# SCH_FMC-R2_MAIN_2026-02-22.net
KiCad netlist of a schematic drawn in EasyEDA
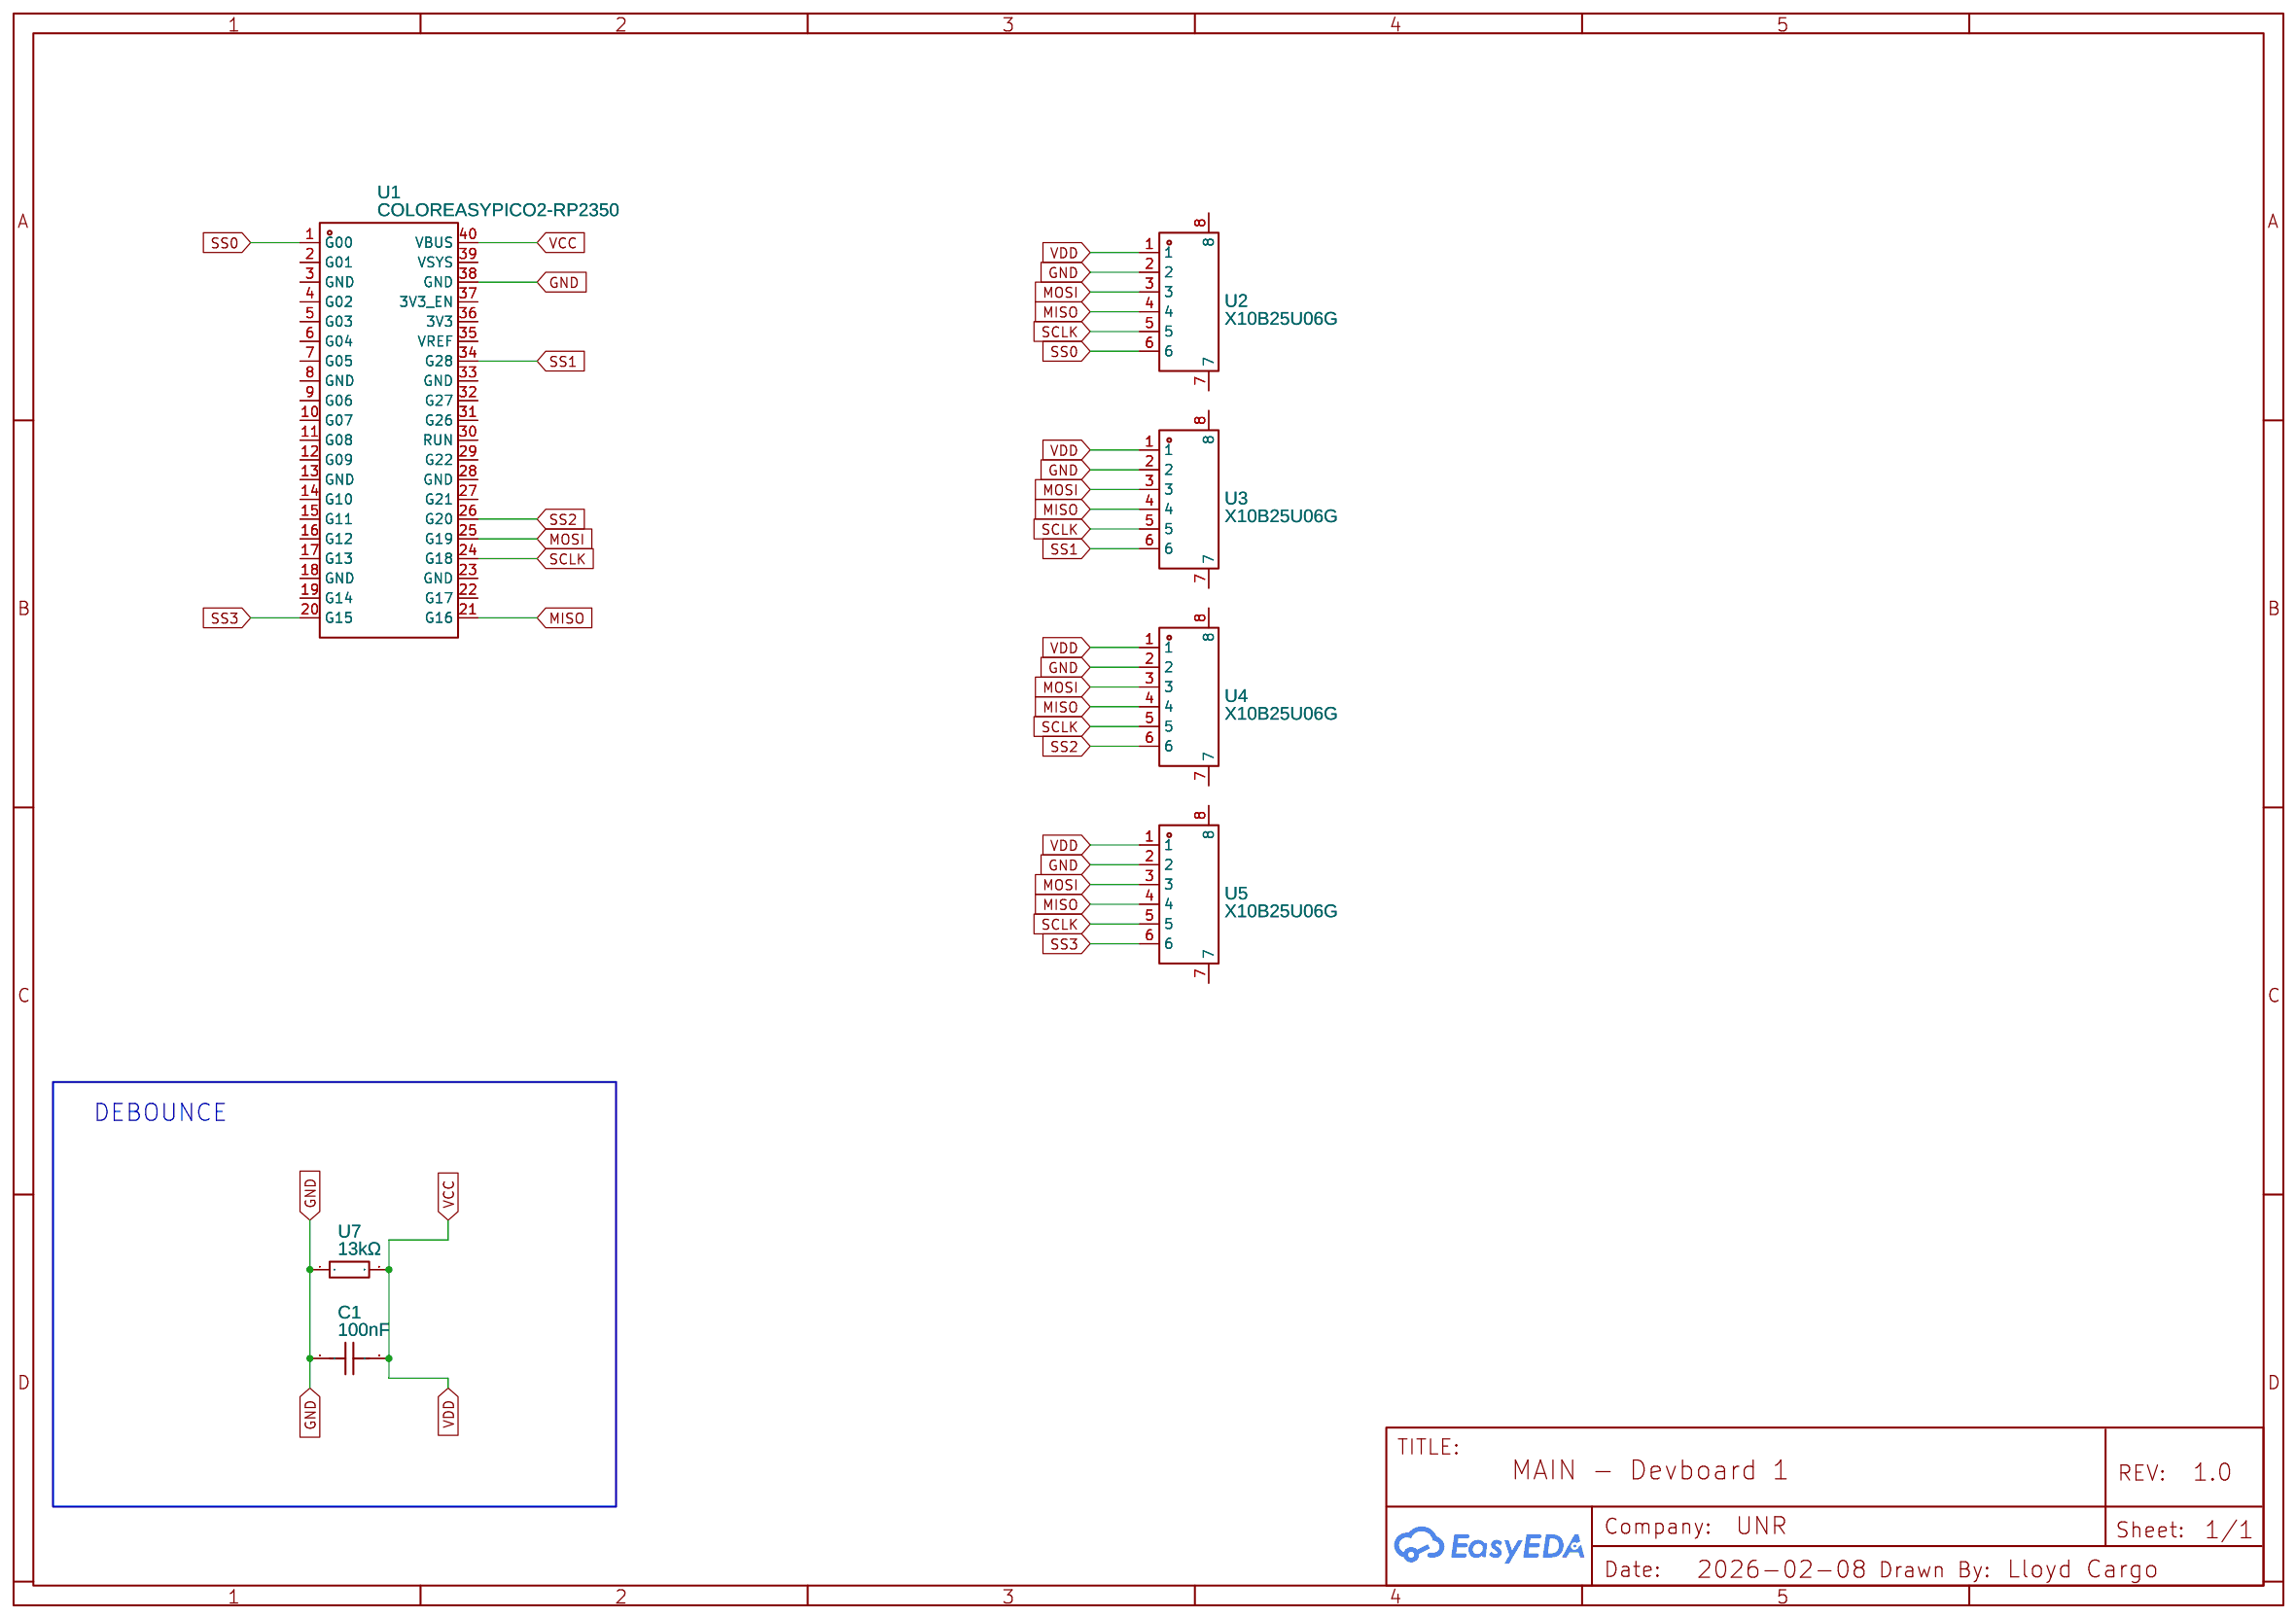
[diagram p0: MAIN]
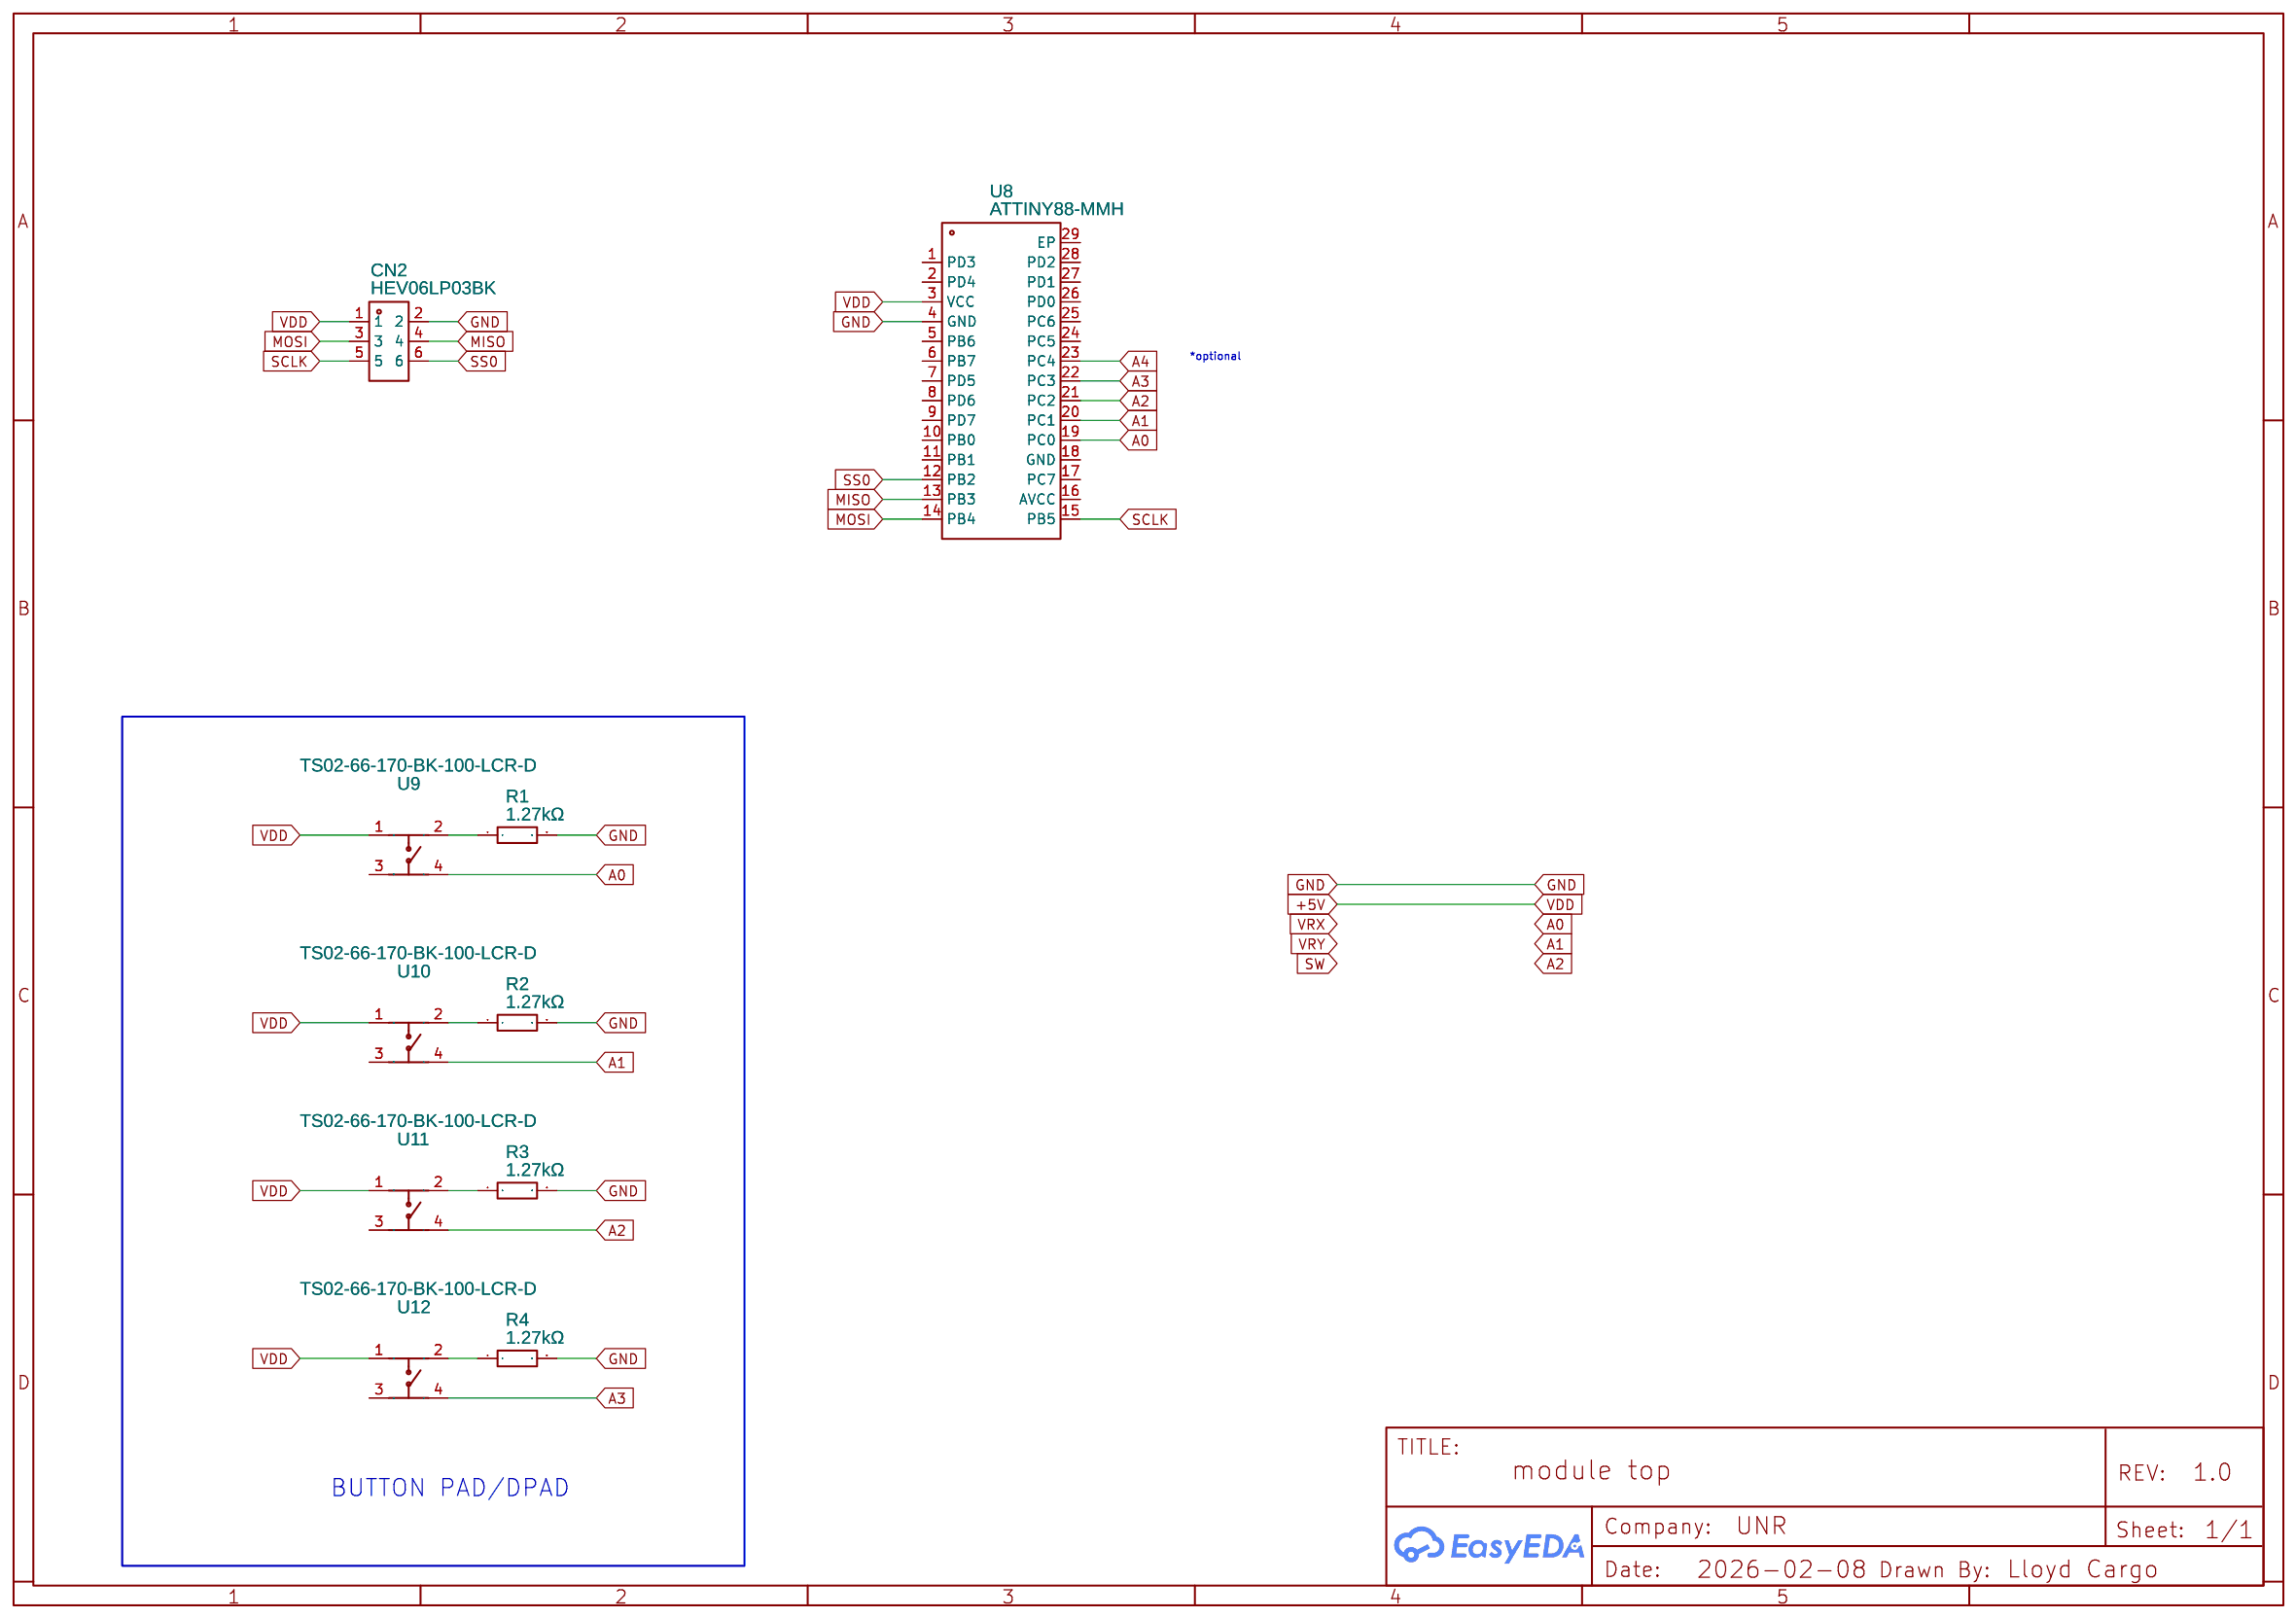
[diagram p1: module top]
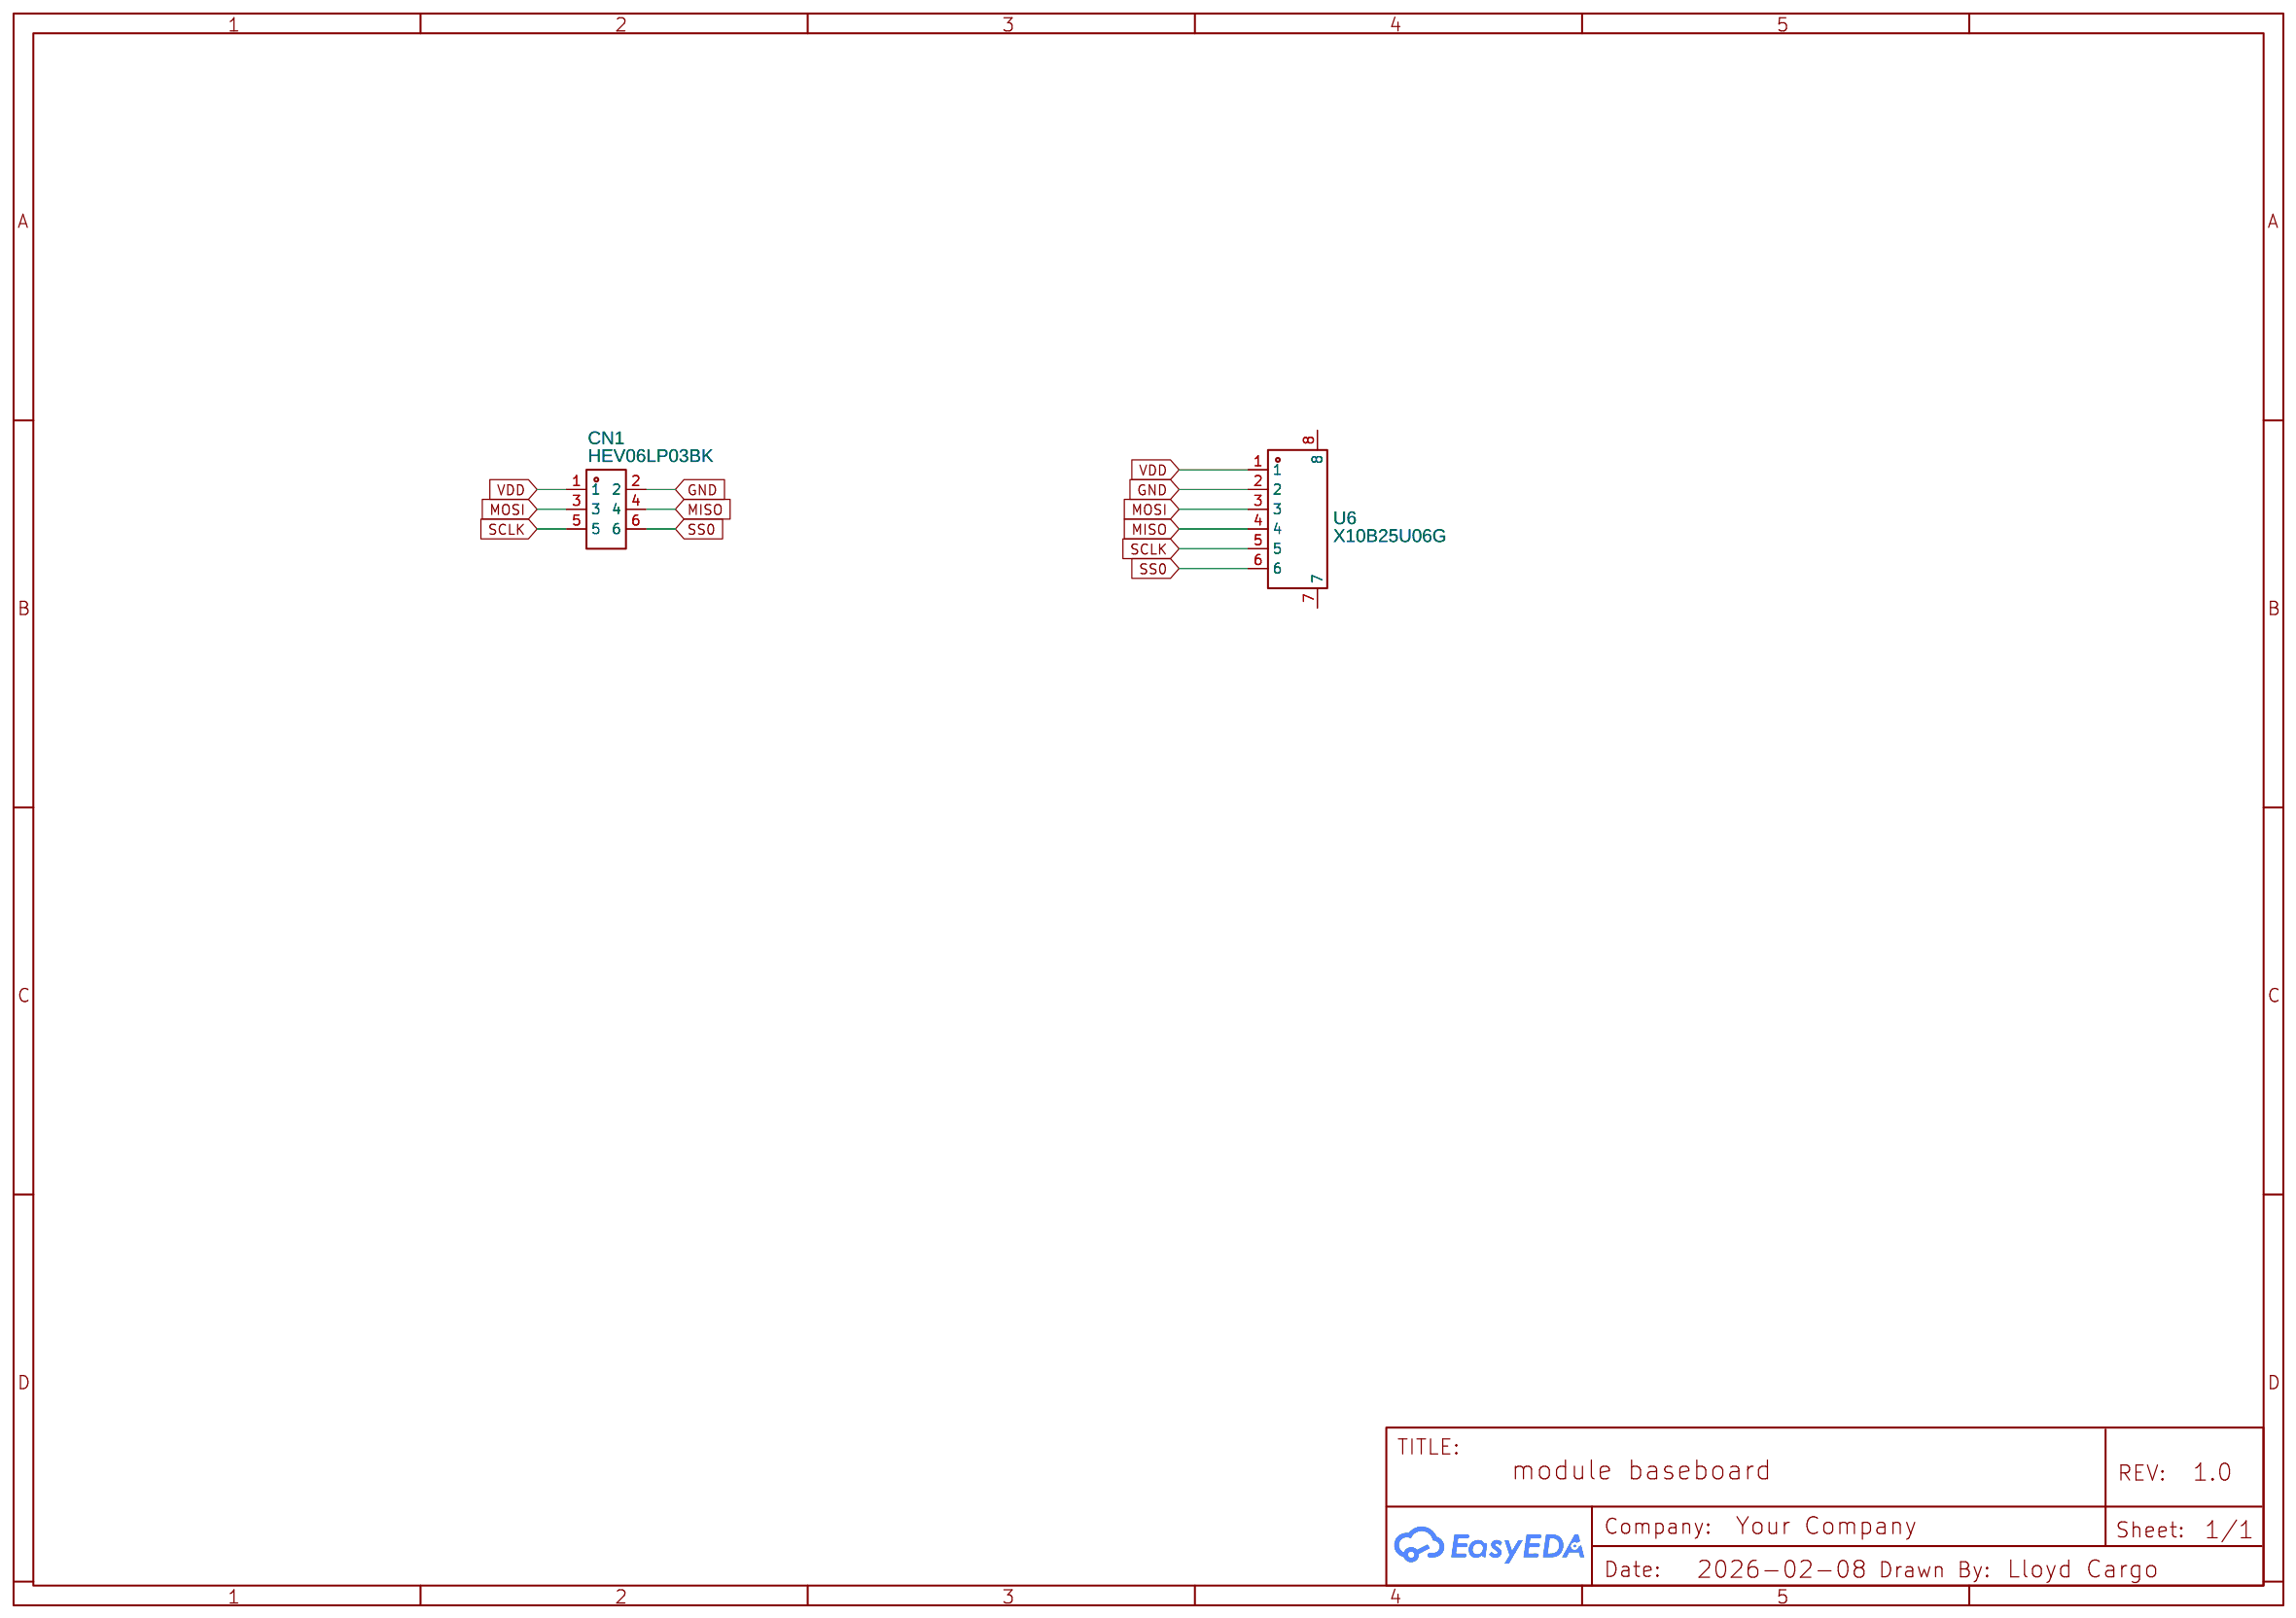
[diagram p2: module baseboard]

(export (version "E")
  (design (tool "Eeschema 10.0.6"))
  (components
    (comp (ref "C1")
      (value "100nF")
      (fields
        (field (name "Manufacturer Part") "GCG188R92A104KA03D")
        (field (name "Manufacturer") "muRata(村田)")
      )
      (libsource (lib "") (part "GCG188R92A104KA03D"))
    )
    (comp (ref "U1")
      (value "COLOREASYPICO2-RP2350")
      (fields
        (field (name "Manufacturer Part") "ColorEasyPico2-RP2350")
        (field (name "Manufacturer") "立创开发板")
      )
      (libsource (lib "") (part "COLOREASYPICO2-RP2350"))
    )
    (comp (ref "U2")
      (value "X10B25U06G")
      (fields (field (name "Manufacturer") "XKB Connection(中国星坤)"))
      (libsource (lib "") (part "X10B25U06G"))
    )
    (comp (ref "U3")
      (value "X10B25U06G")
      (fields (field (name "Manufacturer") "XKB Connection(中国星坤)"))
      (libsource (lib "") (part "X10B25U06G"))
    )
    (comp (ref "U4")
      (value "X10B25U06G")
      (fields (field (name "Manufacturer") "XKB Connection(中国星坤)"))
      (libsource (lib "") (part "X10B25U06G"))
    )
    (comp (ref "U5")
      (value "X10B25U06G")
      (fields (field (name "Manufacturer") "XKB Connection(中国星坤)"))
      (libsource (lib "") (part "X10B25U06G"))
    )
    (comp (ref "U7")
      (value "13kΩ")
      (fields (field (name "Manufacturer Part") "HPCR0805F13K0K9") (field (name "Manufacturer") "RESI(开步睿思)"))
      (libsource (lib "") (part "HPCR0805F13K0K9"))
    )
    (comp (ref "CN2")
      (value "HEV06LP03BK")
      (fields (field (name "Manufacturer") "WingTAT(格林柏)"))
      (libsource (lib "") (part "HEV06LP03BK"))
    )
    (comp (ref "R1")
      (value "1.27kΩ")
      (fields (field (name "Manufacturer Part") "RC0603FR-071K27L") (field (name "Manufacturer") "YAGEO(国巨)"))
      (libsource (lib "") (part "RC0603FR-071K27L"))
    )
    (comp (ref "R2")
      (value "1.27kΩ")
      (fields (field (name "Manufacturer Part") "RC0603FR-071K27L") (field (name "Manufacturer") "YAGEO(国巨)"))
      (libsource (lib "") (part "RC0603FR-071K27L"))
    )
    (comp (ref "R3")
      (value "1.27kΩ")
      (fields (field (name "Manufacturer Part") "RC0603FR-071K27L") (field (name "Manufacturer") "YAGEO(国巨)"))
      (libsource (lib "") (part "RC0603FR-071K27L"))
    )
    (comp (ref "R4")
      (value "1.27kΩ")
      (fields (field (name "Manufacturer Part") "RC0603FR-071K27L") (field (name "Manufacturer") "YAGEO(国巨)"))
      (libsource (lib "") (part "RC0603FR-071K27L"))
    )
    (comp (ref "U8")
      (value "ATTINY88-MMH")
      (fields (field (name "Manufacturer") "MICROCHIP(美国微芯)"))
      (libsource (lib "") (part "ATTINY88-MMH"))
    )
    (comp (ref "U9")
      (value "TS02-66-170-BK-100-LCR-D")
      (fields (field (name "Manufacturer") "CUI"))
      (libsource (lib "") (part "TS02-66-170-BK-100-LCR-D"))
    )
    (comp (ref "U10")
      (value "TS02-66-170-BK-100-LCR-D")
      (fields (field (name "Manufacturer") "CUI"))
      (libsource (lib "") (part "TS02-66-170-BK-100-LCR-D"))
    )
    (comp (ref "U11")
      (value "TS02-66-170-BK-100-LCR-D")
      (fields (field (name "Manufacturer") "CUI"))
      (libsource (lib "") (part "TS02-66-170-BK-100-LCR-D"))
    )
    (comp (ref "U12")
      (value "TS02-66-170-BK-100-LCR-D")
      (fields (field (name "Manufacturer") "CUI"))
      (libsource (lib "") (part "TS02-66-170-BK-100-LCR-D"))
    )
    (comp (ref "CN1")
      (value "HEV06LP03BK")
      (fields (field (name "Manufacturer") "WingTAT(格林柏)"))
      (libsource (lib "") (part "HEV06LP03BK"))
    )
    (comp (ref "U6")
      (value "X10B25U06G")
      (fields (field (name "Manufacturer") "XKB Connection(中国星坤)"))
      (libsource (lib "") (part "X10B25U06G"))
    )
  )
  (nets
    (net (code "1") (name "+5V") (class "Default")
      (node (ref "C1") (pin "2") (pinfunction "2_2") (pintype "unspecified"))
      (node (ref "CN1") (pin "1") (pinfunction "1_1") (pintype "unspecified"))
      (node (ref "CN2") (pin "1") (pinfunction "1_1") (pintype "unspecified"))
      (node (ref "U1") (pin "40") (pinfunction "VBUS_40") (pintype "unspecified"))
      (node (ref "U10") (pin "1") (pinfunction "1_1") (pintype "unspecified"))
      (node (ref "U11") (pin "1") (pinfunction "1_1") (pintype "unspecified"))
      (node (ref "U12") (pin "1") (pinfunction "1_1") (pintype "unspecified"))
      (node (ref "U2") (pin "1") (pinfunction "1_1") (pintype "unspecified"))
      (node (ref "U3") (pin "1") (pinfunction "1_1") (pintype "unspecified"))
      (node (ref "U4") (pin "1") (pinfunction "1_1") (pintype "unspecified"))
      (node (ref "U5") (pin "1") (pinfunction "1_1") (pintype "unspecified"))
      (node (ref "U6") (pin "1") (pinfunction "1_1") (pintype "unspecified"))
      (node (ref "U7") (pin "2") (pinfunction "2_2") (pintype "unspecified"))
      (node (ref "U8") (pin "3") (pinfunction "VCC_3") (pintype "unspecified"))
      (node (ref "U9") (pin "1") (pinfunction "1_1") (pintype "unspecified"))
    )
    (net (code "2") (name "A0") (class "Default")
      (node (ref "U8") (pin "19") (pinfunction "PC0_19") (pintype "unspecified"))
      (node (ref "U9") (pin "4") (pinfunction "4_4") (pintype "unspecified"))
    )
    (net (code "3") (name "A1") (class "Default")
      (node (ref "U10") (pin "4") (pinfunction "4_4") (pintype "unspecified"))
      (node (ref "U8") (pin "20") (pinfunction "PC1_20") (pintype "unspecified"))
    )
    (net (code "4") (name "A2") (class "Default")
      (node (ref "U11") (pin "4") (pinfunction "4_4") (pintype "unspecified"))
      (node (ref "U8") (pin "21") (pinfunction "PC2_21") (pintype "unspecified"))
    )
    (net (code "5") (name "A3") (class "Default")
      (node (ref "U12") (pin "4") (pinfunction "4_4") (pintype "unspecified"))
      (node (ref "U8") (pin "22") (pinfunction "PC3_22") (pintype "unspecified"))
    )
    (net (code "6") (name "A4") (class "Default")
      (node (ref "U8") (pin "23") (pinfunction "PC4_23") (pintype "unspecified"))
    )
    (net (code "7") (name "GND") (class "Default")
      (node (ref "C1") (pin "1") (pinfunction "1_1") (pintype "unspecified"))
      (node (ref "CN1") (pin "2") (pinfunction "2_2") (pintype "unspecified"))
      (node (ref "CN2") (pin "2") (pinfunction "2_2") (pintype "unspecified"))
      (node (ref "R1") (pin "2") (pinfunction "2_2") (pintype "unspecified"))
      (node (ref "R2") (pin "2") (pinfunction "2_2") (pintype "unspecified"))
      (node (ref "R3") (pin "2") (pinfunction "2_2") (pintype "unspecified"))
      (node (ref "R4") (pin "2") (pinfunction "2_2") (pintype "unspecified"))
      (node (ref "U1") (pin "38") (pinfunction "GND_38") (pintype "unspecified"))
      (node (ref "U2") (pin "2") (pinfunction "2_2") (pintype "unspecified"))
      (node (ref "U3") (pin "2") (pinfunction "2_2") (pintype "unspecified"))
      (node (ref "U4") (pin "2") (pinfunction "2_2") (pintype "unspecified"))
      (node (ref "U5") (pin "2") (pinfunction "2_2") (pintype "unspecified"))
      (node (ref "U6") (pin "2") (pinfunction "2_2") (pintype "unspecified"))
      (node (ref "U7") (pin "1") (pinfunction "1_1") (pintype "unspecified"))
      (node (ref "U8") (pin "4") (pinfunction "GND_4") (pintype "unspecified"))
    )
    (net (code "8") (name "MISO") (class "Default")
      (node (ref "CN1") (pin "4") (pinfunction "4_4") (pintype "unspecified"))
      (node (ref "CN2") (pin "4") (pinfunction "4_4") (pintype "unspecified"))
      (node (ref "U1") (pin "21") (pinfunction "G16_21") (pintype "unspecified"))
      (node (ref "U2") (pin "4") (pinfunction "4_4") (pintype "unspecified"))
      (node (ref "U3") (pin "4") (pinfunction "4_4") (pintype "unspecified"))
      (node (ref "U4") (pin "4") (pinfunction "4_4") (pintype "unspecified"))
      (node (ref "U5") (pin "4") (pinfunction "4_4") (pintype "unspecified"))
      (node (ref "U6") (pin "4") (pinfunction "4_4") (pintype "unspecified"))
      (node (ref "U8") (pin "13") (pinfunction "PB3_13") (pintype "unspecified"))
    )
    (net (code "9") (name "MOSI") (class "Default")
      (node (ref "CN1") (pin "3") (pinfunction "3_3") (pintype "unspecified"))
      (node (ref "CN2") (pin "3") (pinfunction "3_3") (pintype "unspecified"))
      (node (ref "U1") (pin "25") (pinfunction "G19_25") (pintype "unspecified"))
      (node (ref "U2") (pin "3") (pinfunction "3_3") (pintype "unspecified"))
      (node (ref "U3") (pin "3") (pinfunction "3_3") (pintype "unspecified"))
      (node (ref "U4") (pin "3") (pinfunction "3_3") (pintype "unspecified"))
      (node (ref "U5") (pin "3") (pinfunction "3_3") (pintype "unspecified"))
      (node (ref "U6") (pin "3") (pinfunction "3_3") (pintype "unspecified"))
      (node (ref "U8") (pin "14") (pinfunction "PB4_14") (pintype "unspecified"))
    )
    (net (code "10") (name "Net-(R1-Pad1)") (class "Default")
      (node (ref "R1") (pin "1") (pinfunction "1_1") (pintype "unspecified"))
      (node (ref "U9") (pin "2") (pinfunction "2_2") (pintype "unspecified"))
    )
    (net (code "11") (name "Net-(R2-Pad1)") (class "Default")
      (node (ref "R2") (pin "1") (pinfunction "1_1") (pintype "unspecified"))
      (node (ref "U10") (pin "2") (pinfunction "2_2") (pintype "unspecified"))
    )
    (net (code "12") (name "Net-(R3-Pad1)") (class "Default")
      (node (ref "R3") (pin "1") (pinfunction "1_1") (pintype "unspecified"))
      (node (ref "U11") (pin "2") (pinfunction "2_2") (pintype "unspecified"))
    )
    (net (code "13") (name "Net-(R4-Pad1)") (class "Default")
      (node (ref "R4") (pin "1") (pinfunction "1_1") (pintype "unspecified"))
      (node (ref "U12") (pin "2") (pinfunction "2_2") (pintype "unspecified"))
    )
    (net (code "14") (name "SCLK") (class "Default")
      (node (ref "CN1") (pin "5") (pinfunction "5_5") (pintype "unspecified"))
      (node (ref "CN2") (pin "5") (pinfunction "5_5") (pintype "unspecified"))
      (node (ref "U1") (pin "24") (pinfunction "G18_24") (pintype "unspecified"))
      (node (ref "U2") (pin "5") (pinfunction "5_5") (pintype "unspecified"))
      (node (ref "U3") (pin "5") (pinfunction "5_5") (pintype "unspecified"))
      (node (ref "U4") (pin "5") (pinfunction "5_5") (pintype "unspecified"))
      (node (ref "U5") (pin "5") (pinfunction "5_5") (pintype "unspecified"))
      (node (ref "U6") (pin "5") (pinfunction "5_5") (pintype "unspecified"))
      (node (ref "U8") (pin "15") (pinfunction "PB5_15") (pintype "unspecified"))
    )
    (net (code "15") (name "SS0") (class "Default")
      (node (ref "CN1") (pin "6") (pinfunction "6_6") (pintype "unspecified"))
      (node (ref "CN2") (pin "6") (pinfunction "6_6") (pintype "unspecified"))
      (node (ref "U1") (pin "1") (pinfunction "G00_1") (pintype "unspecified"))
      (node (ref "U2") (pin "6") (pinfunction "6_6") (pintype "unspecified"))
      (node (ref "U6") (pin "6") (pinfunction "6_6") (pintype "unspecified"))
      (node (ref "U8") (pin "12") (pinfunction "PB2_12") (pintype "unspecified"))
    )
    (net (code "16") (name "SS1") (class "Default")
      (node (ref "U1") (pin "34") (pinfunction "G28_34") (pintype "unspecified"))
      (node (ref "U3") (pin "6") (pinfunction "6_6") (pintype "unspecified"))
    )
    (net (code "17") (name "SS2") (class "Default")
      (node (ref "U1") (pin "26") (pinfunction "G20_26") (pintype "unspecified"))
      (node (ref "U4") (pin "6") (pinfunction "6_6") (pintype "unspecified"))
    )
    (net (code "18") (name "SS3") (class "Default")
      (node (ref "U1") (pin "20") (pinfunction "G15_20") (pintype "unspecified"))
      (node (ref "U5") (pin "6") (pinfunction "6_6") (pintype "unspecified"))
    )
    (net (code "22") (name "unconnected-(U1-3V3-Pad36)") (class "Default")
      (node (ref "U1") (pin "36") (pinfunction "3V3_36") (pintype "unspecified"))
    )
    (net (code "23") (name "unconnected-(U1-3V3_EN-Pad37)") (class "Default")
      (node (ref "U1") (pin "37") (pinfunction "3V3_EN_37") (pintype "unspecified"))
    )
    (net (code "24") (name "unconnected-(U1-G01-Pad2)") (class "Default")
      (node (ref "U1") (pin "2") (pinfunction "G01_2") (pintype "unspecified"))
    )
    (net (code "25") (name "unconnected-(U1-G02-Pad4)") (class "Default")
      (node (ref "U1") (pin "4") (pinfunction "G02_4") (pintype "unspecified"))
    )
    (net (code "26") (name "unconnected-(U1-G03-Pad5)") (class "Default")
      (node (ref "U1") (pin "5") (pinfunction "G03_5") (pintype "unspecified"))
    )
    (net (code "27") (name "unconnected-(U1-G04-Pad6)") (class "Default")
      (node (ref "U1") (pin "6") (pinfunction "G04_6") (pintype "unspecified"))
    )
    (net (code "28") (name "unconnected-(U1-G05-Pad7)") (class "Default")
      (node (ref "U1") (pin "7") (pinfunction "G05_7") (pintype "unspecified"))
    )
    (net (code "29") (name "unconnected-(U1-G06-Pad9)") (class "Default")
      (node (ref "U1") (pin "9") (pinfunction "G06_9") (pintype "unspecified"))
    )
    (net (code "30") (name "unconnected-(U1-G07-Pad10)") (class "Default")
      (node (ref "U1") (pin "10") (pinfunction "G07_10") (pintype "unspecified"))
    )
    (net (code "31") (name "unconnected-(U1-G08-Pad11)") (class "Default")
      (node (ref "U1") (pin "11") (pinfunction "G08_11") (pintype "unspecified"))
    )
    (net (code "32") (name "unconnected-(U1-G09-Pad12)") (class "Default")
      (node (ref "U1") (pin "12") (pinfunction "G09_12") (pintype "unspecified"))
    )
    (net (code "33") (name "unconnected-(U1-G10-Pad14)") (class "Default")
      (node (ref "U1") (pin "14") (pinfunction "G10_14") (pintype "unspecified"))
    )
    (net (code "34") (name "unconnected-(U1-G11-Pad15)") (class "Default")
      (node (ref "U1") (pin "15") (pinfunction "G11_15") (pintype "unspecified"))
    )
    (net (code "35") (name "unconnected-(U1-G12-Pad16)") (class "Default")
      (node (ref "U1") (pin "16") (pinfunction "G12_16") (pintype "unspecified"))
    )
    (net (code "36") (name "unconnected-(U1-G13-Pad17)") (class "Default")
      (node (ref "U1") (pin "17") (pinfunction "G13_17") (pintype "unspecified"))
    )
    (net (code "37") (name "unconnected-(U1-G14-Pad19)") (class "Default")
      (node (ref "U1") (pin "19") (pinfunction "G14_19") (pintype "unspecified"))
    )
    (net (code "38") (name "unconnected-(U1-G17-Pad22)") (class "Default")
      (node (ref "U1") (pin "22") (pinfunction "G17_22") (pintype "unspecified"))
    )
    (net (code "39") (name "unconnected-(U1-G21-Pad27)") (class "Default")
      (node (ref "U1") (pin "27") (pinfunction "G21_27") (pintype "unspecified"))
    )
    (net (code "40") (name "unconnected-(U1-G22-Pad29)") (class "Default")
      (node (ref "U1") (pin "29") (pinfunction "G22_29") (pintype "unspecified"))
    )
    (net (code "41") (name "unconnected-(U1-G26-Pad31)") (class "Default")
      (node (ref "U1") (pin "31") (pinfunction "G26_31") (pintype "unspecified"))
    )
    (net (code "42") (name "unconnected-(U1-G27-Pad32)") (class "Default")
      (node (ref "U1") (pin "32") (pinfunction "G27_32") (pintype "unspecified"))
    )
    (net (code "43") (name "unconnected-(U1-GND-Pad3)") (class "Default")
      (node (ref "U1") (pin "3") (pinfunction "GND_3") (pintype "unspecified"))
    )
    (net (code "44") (name "unconnected-(U1-GND-Pad8)") (class "Default")
      (node (ref "U1") (pin "8") (pinfunction "GND_8") (pintype "unspecified"))
    )
    (net (code "45") (name "unconnected-(U1-GND-Pad13)") (class "Default")
      (node (ref "U1") (pin "13") (pinfunction "GND_13") (pintype "unspecified"))
    )
    (net (code "46") (name "unconnected-(U1-GND-Pad18)") (class "Default")
      (node (ref "U1") (pin "18") (pinfunction "GND_18") (pintype "unspecified"))
    )
    (net (code "47") (name "unconnected-(U1-GND-Pad23)") (class "Default")
      (node (ref "U1") (pin "23") (pinfunction "GND_23") (pintype "unspecified"))
    )
    (net (code "48") (name "unconnected-(U1-GND-Pad28)") (class "Default")
      (node (ref "U1") (pin "28") (pinfunction "GND_28") (pintype "unspecified"))
    )
    (net (code "49") (name "unconnected-(U1-GND-Pad33)") (class "Default")
      (node (ref "U1") (pin "33") (pinfunction "GND_33") (pintype "unspecified"))
    )
    (net (code "50") (name "unconnected-(U1-RUN-Pad30)") (class "Default")
      (node (ref "U1") (pin "30") (pinfunction "RUN_30") (pintype "unspecified"))
    )
    (net (code "51") (name "unconnected-(U1-VREF-Pad35)") (class "Default")
      (node (ref "U1") (pin "35") (pinfunction "VREF_35") (pintype "unspecified"))
    )
    (net (code "52") (name "unconnected-(U1-VSYS-Pad39)") (class "Default")
      (node (ref "U1") (pin "39") (pinfunction "VSYS_39") (pintype "unspecified"))
    )
    (net (code "53") (name "unconnected-(U2-Pad7)") (class "Default")
      (node (ref "U2") (pin "7") (pinfunction "7_7") (pintype "unspecified"))
    )
    (net (code "54") (name "unconnected-(U2-Pad8)") (class "Default")
      (node (ref "U2") (pin "8") (pinfunction "8_8") (pintype "unspecified"))
    )
    (net (code "55") (name "unconnected-(U3-Pad7)") (class "Default")
      (node (ref "U3") (pin "7") (pinfunction "7_7") (pintype "unspecified"))
    )
    (net (code "56") (name "unconnected-(U3-Pad8)") (class "Default")
      (node (ref "U3") (pin "8") (pinfunction "8_8") (pintype "unspecified"))
    )
    (net (code "57") (name "unconnected-(U4-Pad7)") (class "Default")
      (node (ref "U4") (pin "7") (pinfunction "7_7") (pintype "unspecified"))
    )
    (net (code "58") (name "unconnected-(U4-Pad8)") (class "Default")
      (node (ref "U4") (pin "8") (pinfunction "8_8") (pintype "unspecified"))
    )
    (net (code "59") (name "unconnected-(U5-Pad7)") (class "Default")
      (node (ref "U5") (pin "7") (pinfunction "7_7") (pintype "unspecified"))
    )
    (net (code "60") (name "unconnected-(U5-Pad8)") (class "Default")
      (node (ref "U5") (pin "8") (pinfunction "8_8") (pintype "unspecified"))
    )
    (net (code "61") (name "unconnected-(U6-Pad7)") (class "Default")
      (node (ref "U6") (pin "7") (pinfunction "7_7") (pintype "unspecified"))
    )
    (net (code "62") (name "unconnected-(U6-Pad8)") (class "Default")
      (node (ref "U6") (pin "8") (pinfunction "8_8") (pintype "unspecified"))
    )
    (net (code "63") (name "unconnected-(U8-AVCC-Pad16)") (class "Default")
      (node (ref "U8") (pin "16") (pinfunction "AVCC_16") (pintype "unspecified"))
    )
    (net (code "64") (name "unconnected-(U8-EP-Pad29)") (class "Default")
      (node (ref "U8") (pin "29") (pinfunction "EP_29") (pintype "unspecified"))
    )
    (net (code "65") (name "unconnected-(U8-GND-Pad18)") (class "Default")
      (node (ref "U8") (pin "18") (pinfunction "GND_18") (pintype "unspecified"))
    )
    (net (code "66") (name "unconnected-(U8-PB0-Pad10)") (class "Default")
      (node (ref "U8") (pin "10") (pinfunction "PB0_10") (pintype "unspecified"))
    )
    (net (code "67") (name "unconnected-(U8-PB1-Pad11)") (class "Default")
      (node (ref "U8") (pin "11") (pinfunction "PB1_11") (pintype "unspecified"))
    )
    (net (code "68") (name "unconnected-(U8-PB6-Pad5)") (class "Default")
      (node (ref "U8") (pin "5") (pinfunction "PB6_5") (pintype "unspecified"))
    )
    (net (code "69") (name "unconnected-(U8-PB7-Pad6)") (class "Default")
      (node (ref "U8") (pin "6") (pinfunction "PB7_6") (pintype "unspecified"))
    )
    (net (code "70") (name "unconnected-(U8-PC5-Pad24)") (class "Default")
      (node (ref "U8") (pin "24") (pinfunction "PC5_24") (pintype "unspecified"))
    )
    (net (code "71") (name "unconnected-(U8-PC6-Pad25)") (class "Default")
      (node (ref "U8") (pin "25") (pinfunction "PC6_25") (pintype "unspecified"))
    )
    (net (code "72") (name "unconnected-(U8-PC7-Pad17)") (class "Default")
      (node (ref "U8") (pin "17") (pinfunction "PC7_17") (pintype "unspecified"))
    )
    (net (code "73") (name "unconnected-(U8-PD0-Pad26)") (class "Default")
      (node (ref "U8") (pin "26") (pinfunction "PD0_26") (pintype "unspecified"))
    )
    (net (code "74") (name "unconnected-(U8-PD1-Pad27)") (class "Default")
      (node (ref "U8") (pin "27") (pinfunction "PD1_27") (pintype "unspecified"))
    )
    (net (code "75") (name "unconnected-(U8-PD2-Pad28)") (class "Default")
      (node (ref "U8") (pin "28") (pinfunction "PD2_28") (pintype "unspecified"))
    )
    (net (code "76") (name "unconnected-(U8-PD3-Pad1)") (class "Default")
      (node (ref "U8") (pin "1") (pinfunction "PD3_1") (pintype "unspecified"))
    )
    (net (code "77") (name "unconnected-(U8-PD4-Pad2)") (class "Default")
      (node (ref "U8") (pin "2") (pinfunction "PD4_2") (pintype "unspecified"))
    )
    (net (code "78") (name "unconnected-(U8-PD5-Pad7)") (class "Default")
      (node (ref "U8") (pin "7") (pinfunction "PD5_7") (pintype "unspecified"))
    )
    (net (code "79") (name "unconnected-(U8-PD6-Pad8)") (class "Default")
      (node (ref "U8") (pin "8") (pinfunction "PD6_8") (pintype "unspecified"))
    )
    (net (code "80") (name "unconnected-(U8-PD7-Pad9)") (class "Default")
      (node (ref "U8") (pin "9") (pinfunction "PD7_9") (pintype "unspecified"))
    )
    (net (code "81") (name "unconnected-(U9-Pad3)") (class "Default")
      (node (ref "U9") (pin "3") (pinfunction "3_3") (pintype "unspecified"))
    )
    (net (code "82") (name "unconnected-(U10-Pad3)") (class "Default")
      (node (ref "U10") (pin "3") (pinfunction "3_3") (pintype "unspecified"))
    )
    (net (code "83") (name "unconnected-(U11-Pad3)") (class "Default")
      (node (ref "U11") (pin "3") (pinfunction "3_3") (pintype "unspecified"))
    )
    (net (code "84") (name "unconnected-(U12-Pad3)") (class "Default")
      (node (ref "U12") (pin "3") (pinfunction "3_3") (pintype "unspecified"))
    )
  )
)
